# supply.net
KiCad netlist of a schematic drawn in Altium Designer
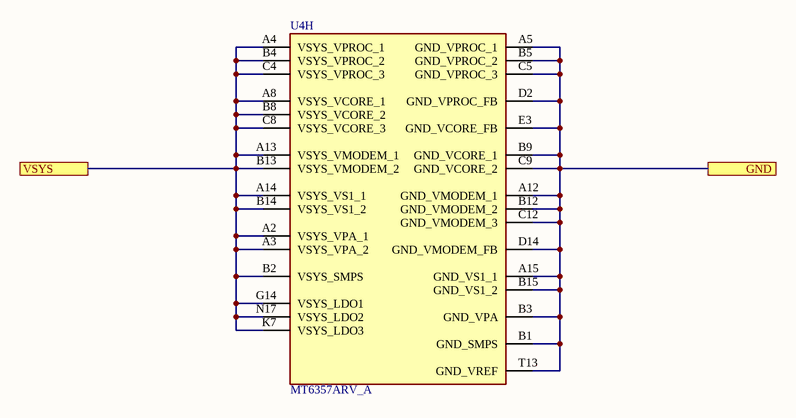
[diagram p0: supply.SchDoc]

(export (version "E")
  (design (tool "Eeschema 10.0.6"))
  (components
    (comp (ref "U4")
      (value "MT6357ARV_A")
      (footprint "BGA209C40P17X16_700X660X100")
      (description "Integrated Circuit")
      (fields
        (field (name "MANUFACTURER_PART_NUMBER") "MT6357ARV/A")
        (field (name "MOUSER PART NUMBER") "840-MT6357ARV/A")
      )
      (libsource (lib "kit") (part "MT6357ARV_A"))
    )
  )
  (nets
    (net (code "1") (name "/GND") (class "Default")
      (node (ref "U4") (pin "A12") (pinfunction "GND_VMODEM_1_A12") (pintype "passive"))
      (node (ref "U4") (pin "A15") (pinfunction "GND_VS1_1_A15") (pintype "passive"))
      (node (ref "U4") (pin "A5") (pinfunction "GND_VPROC_1_A5") (pintype "passive"))
      (node (ref "U4") (pin "B1") (pinfunction "GND_SMPS_B1") (pintype "passive"))
      (node (ref "U4") (pin "B12") (pinfunction "GND_VMODEM_2_B12") (pintype "passive"))
      (node (ref "U4") (pin "B15") (pinfunction "GND_VS1_2_B15") (pintype "passive"))
      (node (ref "U4") (pin "B3") (pinfunction "GND_VPA_B3") (pintype "passive"))
      (node (ref "U4") (pin "B5") (pinfunction "GND_VPROC_2_B5") (pintype "passive"))
      (node (ref "U4") (pin "B9") (pinfunction "GND_VCORE_1_B9") (pintype "passive"))
      (node (ref "U4") (pin "C12") (pinfunction "GND_VMODEM_3_C12") (pintype "passive"))
      (node (ref "U4") (pin "C5") (pinfunction "GND_VPROC_3_C5") (pintype "passive"))
      (node (ref "U4") (pin "C9") (pinfunction "GND_VCORE_2_C9") (pintype "passive"))
      (node (ref "U4") (pin "D14") (pinfunction "GND_VMODEM_FB_D14") (pintype "passive"))
      (node (ref "U4") (pin "D2") (pinfunction "GND_VPROC_FB_D2") (pintype "passive"))
      (node (ref "U4") (pin "E3") (pinfunction "GND_VCORE_FB_E3") (pintype "passive"))
      (node (ref "U4") (pin "T13") (pinfunction "GND_VREF_T13") (pintype "passive"))
    )
    (net (code "2") (name "/VSYS") (class "Default")
      (node (ref "U4") (pin "A13") (pinfunction "VSYS_VMODEM_1_A13") (pintype "passive"))
      (node (ref "U4") (pin "A14") (pinfunction "VSYS_VS1_1_A14") (pintype "passive"))
      (node (ref "U4") (pin "A2") (pinfunction "VSYS_VPA_1_A2") (pintype "passive"))
      (node (ref "U4") (pin "A3") (pinfunction "VSYS_VPA_2_A3") (pintype "passive"))
      (node (ref "U4") (pin "A4") (pinfunction "VSYS_VPROC_1_A4") (pintype "passive"))
      (node (ref "U4") (pin "A8") (pinfunction "VSYS_VCORE_1_A8") (pintype "passive"))
      (node (ref "U4") (pin "B13") (pinfunction "VSYS_VMODEM_2_B13") (pintype "passive"))
      (node (ref "U4") (pin "B14") (pinfunction "VSYS_VS1_2_B14") (pintype "passive"))
      (node (ref "U4") (pin "B2") (pinfunction "VSYS_SMPS_B2") (pintype "passive"))
      (node (ref "U4") (pin "B4") (pinfunction "VSYS_VPROC_2_B4") (pintype "passive"))
      (node (ref "U4") (pin "B8") (pinfunction "VSYS_VCORE_2_B8") (pintype "passive"))
      (node (ref "U4") (pin "C4") (pinfunction "VSYS_VPROC_3_C4") (pintype "passive"))
      (node (ref "U4") (pin "C8") (pinfunction "VSYS_VCORE_3_C8") (pintype "passive"))
      (node (ref "U4") (pin "G14") (pinfunction "VSYS_LDO1_G14") (pintype "passive"))
      (node (ref "U4") (pin "K7") (pinfunction "VSYS_LDO3_K7") (pintype "passive"))
      (node (ref "U4") (pin "N17") (pinfunction "VSYS_LDO2_N17") (pintype "passive"))
    )
  )
)
